# MUX.net
KiCad netlist of a schematic drawn in EAGLE
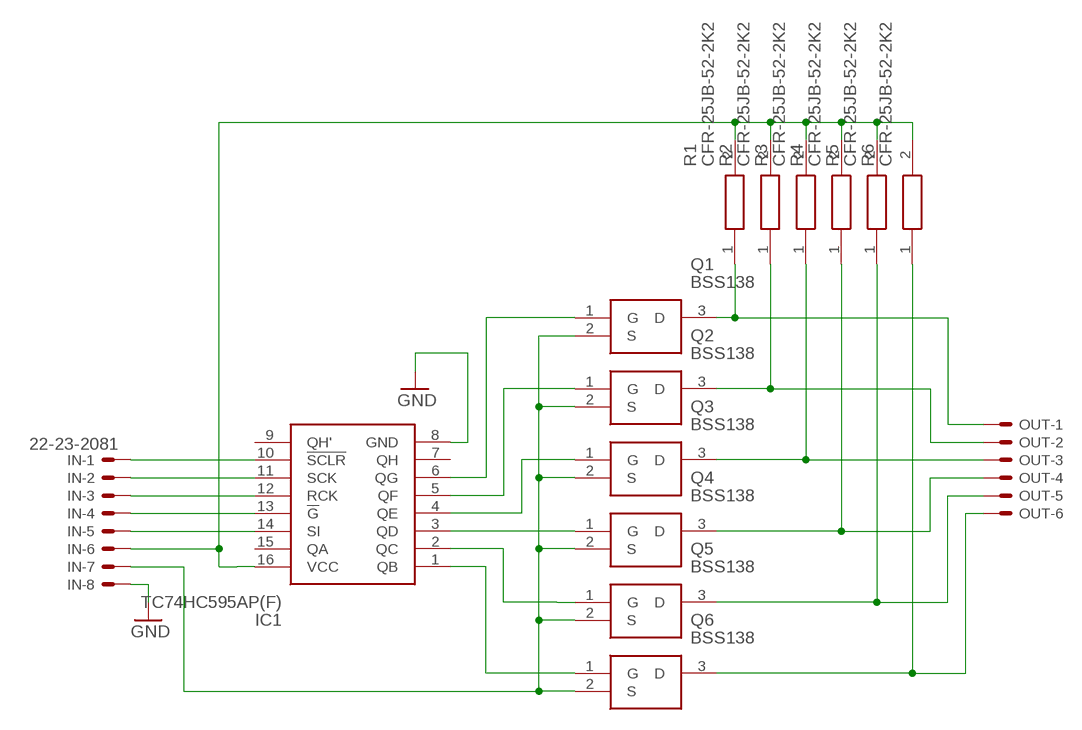
[diagram p0: schematic, sheet 1]

(export (version "E")
  (design (tool "Eeschema 10.0.6"))
  (components
    (comp (ref "IC1")
      (value "TC74HC595AP(F)")
      (footprint "eagle-import:DIP762W60P254L1925H445Q16N")
      (fields (field (name "RS_PART_NUMBER") "5400095P"))
      (libsource (lib "eagle-import") (part "TC74HC595AP(F)"))
    )
    (comp (ref "IN")
      (value "22-23-2081")
      (footprint "eagle-import:22-23-2081")
      (fields (field (name "MF") "MOLEX"))
      (libsource (lib "eagle-import") (part "22-23-2081"))
    )
    (comp (ref "OUT")
      (value "22-23-2061")
      (footprint "eagle-import:22-23-2061")
      (fields (field (name "MF") "MOLEX"))
      (libsource (lib "eagle-import") (part "22-23-2061"))
    )
    (comp (ref "Q1")
      (value "BSS138")
      (footprint "eagle-import:SOT95P240X120-3N")
      (fields (field (name "MOUSER_PART_NUMBER") "512-BSS138") (field (name "RS_PART_NUMBER") "1241694"))
      (libsource (lib "eagle-import") (part "BSS138"))
    )
    (comp (ref "Q2")
      (value "BSS138")
      (footprint "eagle-import:SOT95P240X120-3N")
      (fields (field (name "MOUSER_PART_NUMBER") "512-BSS138") (field (name "RS_PART_NUMBER") "1241694"))
      (libsource (lib "eagle-import") (part "BSS138"))
    )
    (comp (ref "Q3")
      (value "BSS138")
      (footprint "eagle-import:SOT95P240X120-3N")
      (fields (field (name "MOUSER_PART_NUMBER") "512-BSS138") (field (name "RS_PART_NUMBER") "1241694"))
      (libsource (lib "eagle-import") (part "BSS138"))
    )
    (comp (ref "Q4")
      (value "BSS138")
      (footprint "eagle-import:SOT95P240X120-3N")
      (fields (field (name "MOUSER_PART_NUMBER") "512-BSS138") (field (name "RS_PART_NUMBER") "1241694"))
      (libsource (lib "eagle-import") (part "BSS138"))
    )
    (comp (ref "Q5")
      (value "BSS138")
      (footprint "eagle-import:SOT95P240X120-3N")
      (fields (field (name "MOUSER_PART_NUMBER") "512-BSS138") (field (name "RS_PART_NUMBER") "1241694"))
      (libsource (lib "eagle-import") (part "BSS138"))
    )
    (comp (ref "Q6")
      (value "BSS138")
      (footprint "eagle-import:SOT95P240X120-3N")
      (fields (field (name "MOUSER_PART_NUMBER") "512-BSS138") (field (name "RS_PART_NUMBER") "1241694"))
      (libsource (lib "eagle-import") (part "BSS138"))
    )
    (comp (ref "R1")
      (value "CFR-25JB-52-2K2")
      (footprint "eagle-import:RESAD1590W60L630D240")
      (fields (field (name "MOUSER_PART_NUMBER") "603-CFR-25JB-52-2K2"))
      (libsource (lib "eagle-import") (part "CFR-25JB-52-2K2"))
    )
    (comp (ref "R2")
      (value "CFR-25JB-52-2K2")
      (footprint "eagle-import:RESAD1590W60L630D240")
      (fields (field (name "MOUSER_PART_NUMBER") "603-CFR-25JB-52-2K2"))
      (libsource (lib "eagle-import") (part "CFR-25JB-52-2K2"))
    )
    (comp (ref "R3")
      (value "CFR-25JB-52-2K2")
      (footprint "eagle-import:RESAD1590W60L630D240")
      (fields (field (name "MOUSER_PART_NUMBER") "603-CFR-25JB-52-2K2"))
      (libsource (lib "eagle-import") (part "CFR-25JB-52-2K2"))
    )
    (comp (ref "R4")
      (value "CFR-25JB-52-2K2")
      (footprint "eagle-import:RESAD1590W60L630D240")
      (fields (field (name "MOUSER_PART_NUMBER") "603-CFR-25JB-52-2K2"))
      (libsource (lib "eagle-import") (part "CFR-25JB-52-2K2"))
    )
    (comp (ref "R5")
      (value "CFR-25JB-52-2K2")
      (footprint "eagle-import:RESAD1590W60L630D240")
      (fields (field (name "MOUSER_PART_NUMBER") "603-CFR-25JB-52-2K2"))
      (libsource (lib "eagle-import") (part "CFR-25JB-52-2K2"))
    )
    (comp (ref "R6")
      (value "CFR-25JB-52-2K2")
      (footprint "eagle-import:RESAD1590W60L630D240")
      (fields (field (name "MOUSER_PART_NUMBER") "603-CFR-25JB-52-2K2"))
      (libsource (lib "eagle-import") (part "CFR-25JB-52-2K2"))
    )
  )
  (nets
    (net (code "1") (name "GND") (class "Default")
      (node (ref "IC1") (pin "8") (pinfunction "GND_8") (pintype "bidirectional"))
      (node (ref "IN") (pin "8") (pinfunction "S_8") (pintype "passive"))
    )
    (net (code "2") (name "Net-(IC1-QB)") (class "Default")
      (node (ref "IC1") (pin "1") (pinfunction "QB_1") (pintype "bidirectional"))
      (node (ref "Q6") (pin "1") (pinfunction "G_1") (pintype "bidirectional"))
    )
    (net (code "3") (name "Net-(IC1-QC)") (class "Default")
      (node (ref "IC1") (pin "2") (pinfunction "QC_2") (pintype "bidirectional"))
      (node (ref "Q5") (pin "1") (pinfunction "G_1") (pintype "bidirectional"))
    )
    (net (code "4") (name "Net-(IC1-QD)") (class "Default")
      (node (ref "IC1") (pin "3") (pinfunction "QD_3") (pintype "bidirectional"))
      (node (ref "Q4") (pin "1") (pinfunction "G_1") (pintype "bidirectional"))
    )
    (net (code "5") (name "Net-(IC1-QE)") (class "Default")
      (node (ref "IC1") (pin "4") (pinfunction "QE_4") (pintype "bidirectional"))
      (node (ref "Q3") (pin "1") (pinfunction "G_1") (pintype "bidirectional"))
    )
    (net (code "6") (name "Net-(IC1-QF)") (class "Default")
      (node (ref "IC1") (pin "5") (pinfunction "QF_5") (pintype "bidirectional"))
      (node (ref "Q2") (pin "1") (pinfunction "G_1") (pintype "bidirectional"))
    )
    (net (code "7") (name "Net-(IC1-QG)") (class "Default")
      (node (ref "IC1") (pin "6") (pinfunction "QG_6") (pintype "bidirectional"))
      (node (ref "Q1") (pin "1") (pinfunction "G_1") (pintype "bidirectional"))
    )
    (net (code "8") (name "Net-(IC1-RCK)") (class "Default")
      (node (ref "IC1") (pin "12") (pinfunction "RCK_12") (pintype "bidirectional"))
      (node (ref "IN") (pin "3") (pinfunction "S_3") (pintype "passive"))
    )
    (net (code "9") (name "Net-(IC1-SCK)") (class "Default")
      (node (ref "IC1") (pin "11") (pinfunction "SCK_11") (pintype "bidirectional"))
      (node (ref "IN") (pin "2") (pinfunction "S_2") (pintype "passive"))
    )
    (net (code "10") (name "Net-(IC1-SI)") (class "Default")
      (node (ref "IC1") (pin "14") (pinfunction "SI_14") (pintype "bidirectional"))
      (node (ref "IN") (pin "5") (pinfunction "S_5") (pintype "passive"))
    )
    (net (code "11") (name "Net-(IC1-VCC)") (class "Default")
      (node (ref "IC1") (pin "16") (pinfunction "VCC_16") (pintype "bidirectional"))
      (node (ref "IN") (pin "6") (pinfunction "S_6") (pintype "passive"))
      (node (ref "R1") (pin "2") (pinfunction "2_2") (pintype "bidirectional"))
      (node (ref "R2") (pin "2") (pinfunction "2_2") (pintype "bidirectional"))
      (node (ref "R3") (pin "2") (pinfunction "2_2") (pintype "bidirectional"))
      (node (ref "R4") (pin "2") (pinfunction "2_2") (pintype "bidirectional"))
      (node (ref "R5") (pin "2") (pinfunction "2_2") (pintype "bidirectional"))
      (node (ref "R6") (pin "2") (pinfunction "2_2") (pintype "bidirectional"))
    )
    (net (code "12") (name "Net-(IC1-~{G})") (class "Default")
      (node (ref "IC1") (pin "13") (pinfunction "~{G}_13") (pintype "bidirectional"))
      (node (ref "IN") (pin "4") (pinfunction "S_4") (pintype "passive"))
    )
    (net (code "13") (name "Net-(IC1-~{SCLR})") (class "Default")
      (node (ref "IC1") (pin "10") (pinfunction "~{SCLR}_10") (pintype "bidirectional"))
      (node (ref "IN") (pin "1") (pinfunction "S_1") (pintype "passive"))
    )
    (net (code "14") (name "Net-(ING-S)") (class "Default")
      (node (ref "IN") (pin "7") (pinfunction "S_7") (pintype "passive"))
      (node (ref "Q1") (pin "2") (pinfunction "S_2") (pintype "bidirectional"))
      (node (ref "Q2") (pin "2") (pinfunction "S_2") (pintype "bidirectional"))
      (node (ref "Q3") (pin "2") (pinfunction "S_2") (pintype "bidirectional"))
      (node (ref "Q4") (pin "2") (pinfunction "S_2") (pintype "bidirectional"))
      (node (ref "Q5") (pin "2") (pinfunction "S_2") (pintype "bidirectional"))
      (node (ref "Q6") (pin "2") (pinfunction "S_2") (pintype "bidirectional"))
    )
    (net (code "15") (name "Net-(OUTA-S)") (class "Default")
      (node (ref "OUT") (pin "1") (pinfunction "S_1") (pintype "passive"))
      (node (ref "Q1") (pin "3") (pinfunction "D_3") (pintype "bidirectional"))
      (node (ref "R1") (pin "1") (pinfunction "1_1") (pintype "bidirectional"))
    )
    (net (code "16") (name "Net-(OUTB-S)") (class "Default")
      (node (ref "OUT") (pin "2") (pinfunction "S_2") (pintype "passive"))
      (node (ref "Q2") (pin "3") (pinfunction "D_3") (pintype "bidirectional"))
      (node (ref "R2") (pin "1") (pinfunction "1_1") (pintype "bidirectional"))
    )
    (net (code "17") (name "Net-(OUTC-S)") (class "Default")
      (node (ref "OUT") (pin "3") (pinfunction "S_3") (pintype "passive"))
      (node (ref "Q3") (pin "3") (pinfunction "D_3") (pintype "bidirectional"))
      (node (ref "R3") (pin "1") (pinfunction "1_1") (pintype "bidirectional"))
    )
    (net (code "18") (name "Net-(OUTD-S)") (class "Default")
      (node (ref "OUT") (pin "4") (pinfunction "S_4") (pintype "passive"))
      (node (ref "Q4") (pin "3") (pinfunction "D_3") (pintype "bidirectional"))
      (node (ref "R4") (pin "1") (pinfunction "1_1") (pintype "bidirectional"))
    )
    (net (code "19") (name "Net-(OUTE-S)") (class "Default")
      (node (ref "OUT") (pin "5") (pinfunction "S_5") (pintype "passive"))
      (node (ref "Q5") (pin "3") (pinfunction "D_3") (pintype "bidirectional"))
      (node (ref "R5") (pin "1") (pinfunction "1_1") (pintype "bidirectional"))
    )
    (net (code "20") (name "Net-(OUTF-S)") (class "Default")
      (node (ref "OUT") (pin "6") (pinfunction "S_6") (pintype "passive"))
      (node (ref "Q6") (pin "3") (pinfunction "D_3") (pintype "bidirectional"))
      (node (ref "R6") (pin "1") (pinfunction "1_1") (pintype "bidirectional"))
    )
    (net (code "21") (name "unconnected-(IC1-QA-Pad15)") (class "Default")
      (node (ref "IC1") (pin "15") (pinfunction "QA_15") (pintype "bidirectional"))
    )
    (net (code "22") (name "unconnected-(IC1-QH'-Pad9)") (class "Default")
      (node (ref "IC1") (pin "9") (pinfunction "QH'_9") (pintype "bidirectional"))
    )
    (net (code "23") (name "unconnected-(IC1-QH-Pad7)") (class "Default")
      (node (ref "IC1") (pin "7") (pinfunction "QH_7") (pintype "bidirectional"))
    )
  )
)
